# CAN.net
KiCad netlist of a schematic drawn in Altium Designer
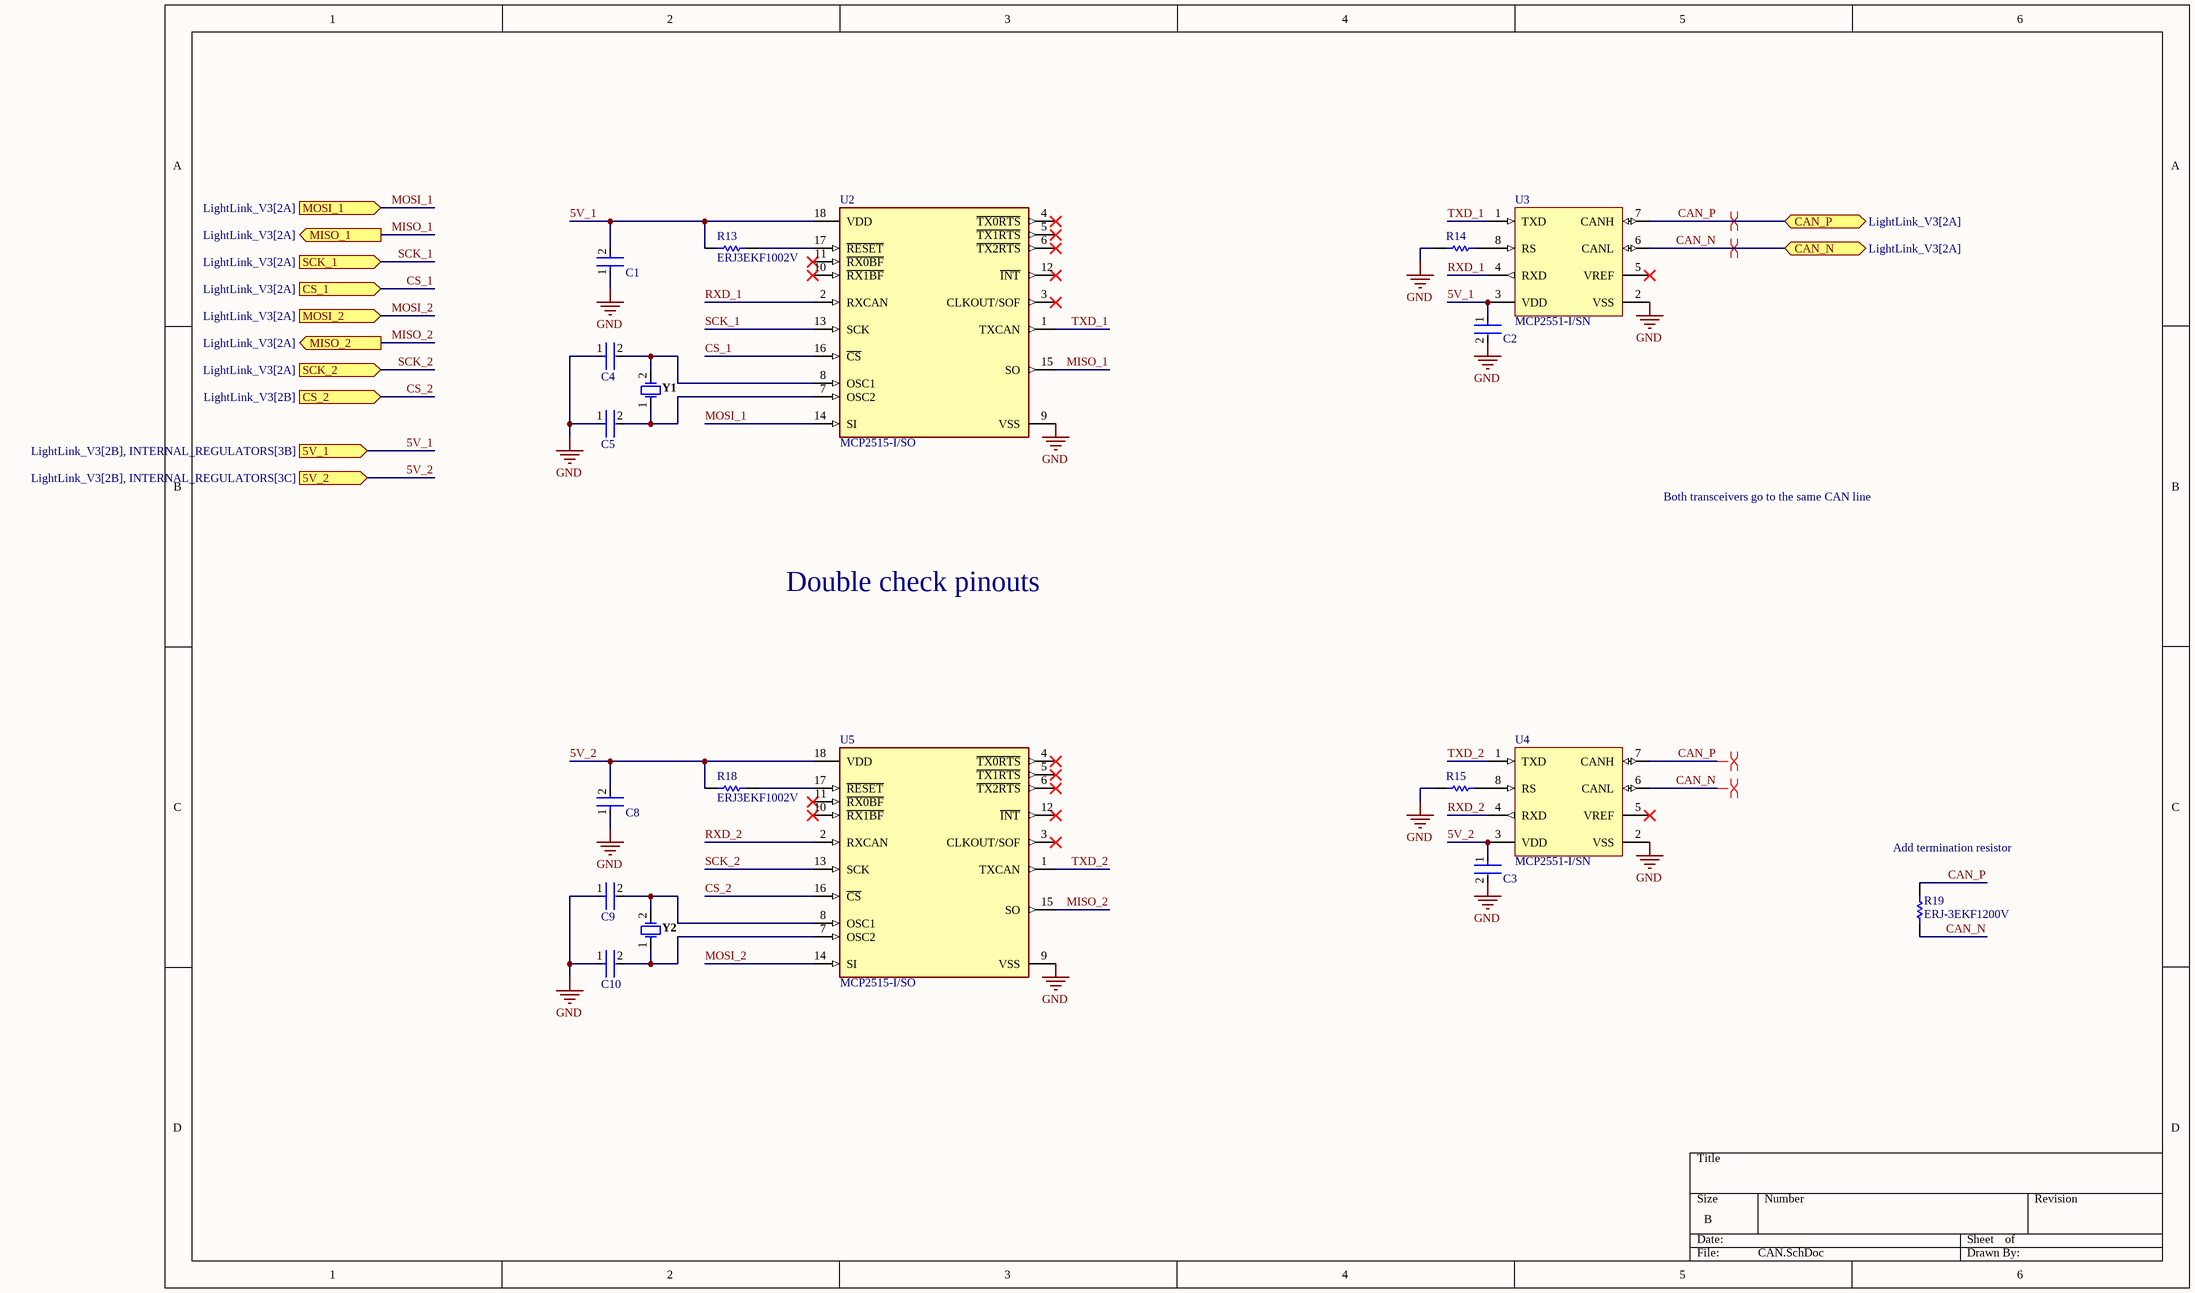
[diagram p0: CAN.SchDoc]

(export (version "E")
  (design (tool "Eeschema 10.0.6"))
  (components
    (comp (ref "C1")
      (value "GRM188R60J106ME47D")
      (footprint "FP-GRM188-0_1-e0_2_0_55-IPC_A")
      (description "Chip Multilayer Ceramic Capacitors for General Purpose, 0603, 10uF, X5R, 15%, 20%, 6.3V")
      (fields (field (name "VOLTAGE") "6.3V") (field (name "TOLERANCE") "20%"))
      (libsource (lib "Altium Content Vault") (part "02cd4be3c70576c341d710602a673aa"))
    )
    (comp (ref "C2")
      (value "C0402C104K8PACTU")
      (footprint "FP-C0402-BB-MFG")
      (description "CAP CER 0.1UF 10V X5R 0402")
      (fields (field (name "MANUFACTURER") "Kemet") (field (name "TOLERANCE") "0.1"))
      (libsource (lib "Altium Content Vault") (part "b4654b650e69147ec39a6b967a45e02"))
    )
    (comp (ref "C3")
      (value "C0402C104K8PACTU")
      (footprint "FP-C0402-BB-MFG")
      (description "CAP CER 0.1UF 10V X5R 0402")
      (fields (field (name "MANUFACTURER") "Kemet") (field (name "TOLERANCE") "0.1"))
      (libsource (lib "Altium Content Vault") (part "b4654b650e69147ec39a6b967a45e02"))
    )
    (comp (ref "C4")
      (value "GRM188R60J106ME47D")
      (footprint "FP-GRM188-0_1-e0_2_0_55-IPC_A")
      (description "Chip Multilayer Ceramic Capacitors for General Purpose, 0603, 10uF, X5R, 15%, 20%, 6.3V")
      (fields (field (name "VOLTAGE") "6.3V") (field (name "TOLERANCE") "20%"))
      (libsource (lib "Altium Content Vault") (part "02cd4be3c70576c341d710602a673aa"))
    )
    (comp (ref "C5")
      (value "GRM188R60J106ME47D")
      (footprint "FP-GRM188-0_1-e0_2_0_55-IPC_A")
      (description "Chip Multilayer Ceramic Capacitors for General Purpose, 0603, 10uF, X5R, 15%, 20%, 6.3V")
      (fields (field (name "VOLTAGE") "6.3V") (field (name "TOLERANCE") "20%"))
      (libsource (lib "Altium Content Vault") (part "02cd4be3c70576c341d710602a673aa"))
    )
    (comp (ref "C8")
      (value "GRM188R60J106ME47D")
      (footprint "FP-GRM188-0_1-e0_2_0_55-IPC_A")
      (description "Chip Multilayer Ceramic Capacitors for General Purpose, 0603, 10uF, X5R, 15%, 20%, 6.3V")
      (fields (field (name "VOLTAGE") "6.3V") (field (name "TOLERANCE") "20%"))
      (libsource (lib "Altium Content Vault") (part "02cd4be3c70576c341d710602a673aa"))
    )
    (comp (ref "C9")
      (value "GRM188R60J106ME47D")
      (footprint "FP-GRM188-0_1-e0_2_0_55-IPC_A")
      (description "Chip Multilayer Ceramic Capacitors for General Purpose, 0603, 10uF, X5R, 15%, 20%, 6.3V")
      (fields (field (name "VOLTAGE") "6.3V") (field (name "TOLERANCE") "20%"))
      (libsource (lib "Altium Content Vault") (part "02cd4be3c70576c341d710602a673aa"))
    )
    (comp (ref "C10")
      (value "GRM188R60J106ME47D")
      (footprint "FP-GRM188-0_1-e0_2_0_55-IPC_A")
      (description "Chip Multilayer Ceramic Capacitors for General Purpose, 0603, 10uF, X5R, 15%, 20%, 6.3V")
      (fields (field (name "VOLTAGE") "6.3V") (field (name "TOLERANCE") "20%"))
      (libsource (lib "Altium Content Vault") (part "02cd4be3c70576c341d710602a673aa"))
    )
    (comp (ref "R13")
      (value "ERJ3EKF1002V")
      (footprint "RESC1609X55X30LL15T15")
      (description "Chip Resistor, 10 KOhm, +/- 1%, 0.1 W, -55 to 155 degC, 0603 (1608 Metric), RoHS, Tape and Reel")
      (fields (field (name "TOLERANCE") "1%") (field (name "MANUFACTURER") "Panasonic"))
      (libsource (lib "Altium Content Vault") (part "RES-2"))
    )
    (comp (ref "R14")
      (value "ERJ3EKF1002V")
      (footprint "RESC1609X55X30LL15T15")
      (description "Chip Resistor, 10 KOhm, +/- 1%, 0.1 W, -55 to 155 degC, 0603 (1608 Metric), RoHS, Tape and Reel")
      (fields (field (name "TOLERANCE") "1%") (field (name "MANUFACTURER") "Panasonic"))
      (libsource (lib "Altium Content Vault") (part "RES-2"))
    )
    (comp (ref "R15")
      (value "ERJ3EKF1002V")
      (footprint "RESC1609X55X30LL15T15")
      (description "Chip Resistor, 10 KOhm, +/- 1%, 0.1 W, -55 to 155 degC, 0603 (1608 Metric), RoHS, Tape and Reel")
      (fields (field (name "TOLERANCE") "1%") (field (name "MANUFACTURER") "Panasonic"))
      (libsource (lib "Altium Content Vault") (part "RES-2"))
    )
    (comp (ref "R18")
      (value "ERJ3EKF1002V")
      (footprint "RESC1609X55X30LL15T15")
      (description "Chip Resistor, 10 KOhm, +/- 1%, 0.1 W, -55 to 155 degC, 0603 (1608 Metric), RoHS, Tape and Reel")
      (fields (field (name "TOLERANCE") "1%") (field (name "MANUFACTURER") "Panasonic"))
      (libsource (lib "Altium Content Vault") (part "RES-2"))
    )
    (comp (ref "R19")
      (value "ERJ-3EKF1200V")
      (footprint "RESC1609X55X30ML15T15")
      (description "Chip Resistor, 120 Ohm, +/- 1%, 0.1 W, -55 to 155 degC, 0603 (1608 Metric), RoHS, Tape and Reel")
      (fields (field (name "TOLERANCE") "1%") (field (name "MANUFACTURER") "Panasonic"))
      (libsource (lib "Altium Content Vault") (part "RES-2"))
    )
    (comp (ref "U2")
      (value "MCP2515-I/SO")
      (footprint "FP-C04-051-MFG")
      (description "IC CAN CONTROLLER W/SPI 18SOIC")
      (fields
        (field (name "MANUFACTURER") "Microchip")
        (field (name "OCTOPART") "https://octopart.com/mcp2515-i%2Fso-microchip-430187")
      )
      (libsource (lib "Altium Content Vault") (part "1c78ea6ff576bac94664e2637e1b479"))
    )
    (comp (ref "U3")
      (value "MCP2551-I/SN")
      (footprint "MCHP-SN8_V")
      (fields (field (name "MANUFACTURER") "Microchip"))
      (libsource (lib "Altium Content Vault") (part "MCHP-MCP2551-SN8"))
    )
    (comp (ref "U4")
      (value "MCP2551-I/SN")
      (footprint "MCHP-SN8_V")
      (fields (field (name "MANUFACTURER") "Microchip"))
      (libsource (lib "Altium Content Vault") (part "MCHP-MCP2551-SN8"))
    )
    (comp (ref "U5")
      (value "MCP2515-I/SO")
      (footprint "FP-C04-051-MFG")
      (description "IC CAN CONTROLLER W/SPI 18SOIC")
      (fields
        (field (name "MANUFACTURER") "Microchip")
        (field (name "OCTOPART") "https://octopart.com/mcp2515-i%2Fso-microchip-430187")
      )
      (libsource (lib "Altium Content Vault") (part "1c78ea6ff576bac94664e2637e1b479"))
    )
    (comp (ref "Y1")
      (value "FOXSLF/160-20")
      (footprint "FOX-FOXSLF160-20")
      (description "Resistance Weld Thru-Hole Crystal, 16 MHz, -20 to 70 degC, 2-Pin THD, RoHS, Bulk")
      (fields (field (name "TOLERANCE") "1%"))
      (libsource (lib "Altium Content Vault") (part "XTAL-1-2-2"))
    )
    (comp (ref "Y2")
      (value "FOXSLF/160-20")
      (footprint "FOX-FOXSLF160-20")
      (description "Resistance Weld Thru-Hole Crystal, 16 MHz, -20 to 70 degC, 2-Pin THD, RoHS, Bulk")
      (fields (field (name "TOLERANCE") "1%"))
      (libsource (lib "Altium Content Vault") (part "XTAL-1-2-2"))
    )
  )
  (nets
    (net (code "1") (name "/5V_1") (class "Default")
      (node (ref "C1") (pin "2") (pinfunction "2_2") (pintype "passive"))
      (node (ref "C2") (pin "1") (pinfunction "1_1") (pintype "passive"))
      (node (ref "R13") (pin "1") (pinfunction "1_1") (pintype "passive"))
      (node (ref "U2") (pin "18") (pinfunction "VDD_18") (pintype "power_in"))
      (node (ref "U3") (pin "3") (pinfunction "VDD_3") (pintype "power_in"))
    )
    (net (code "2") (name "/5V_2") (class "Default")
      (node (ref "C3") (pin "1") (pinfunction "1_1") (pintype "passive"))
      (node (ref "C8") (pin "2") (pinfunction "2_2") (pintype "passive"))
      (node (ref "R18") (pin "1") (pinfunction "1_1") (pintype "passive"))
      (node (ref "U4") (pin "3") (pinfunction "VDD_3") (pintype "power_in"))
      (node (ref "U5") (pin "18") (pinfunction "VDD_18") (pintype "power_in"))
    )
    (net (code "3") (name "/CAN_N") (class "Default")
      (node (ref "R19") (pin "1") (pinfunction "1_1") (pintype "passive"))
      (node (ref "U3") (pin "6") (pinfunction "CANL_6") (pintype "bidirectional"))
      (node (ref "U4") (pin "6") (pinfunction "CANL_6") (pintype "bidirectional"))
    )
    (net (code "4") (name "/CAN_P") (class "Default")
      (node (ref "R19") (pin "2") (pinfunction "2_2") (pintype "passive"))
      (node (ref "U3") (pin "7") (pinfunction "CANH_7") (pintype "bidirectional"))
      (node (ref "U4") (pin "7") (pinfunction "CANH_7") (pintype "bidirectional"))
    )
    (net (code "5") (name "/CS_1") (class "Default")
      (node (ref "U2") (pin "16") (pinfunction "~{CS}_16") (pintype "input"))
    )
    (net (code "6") (name "/CS_2") (class "Default")
      (node (ref "U5") (pin "16") (pinfunction "~{CS}_16") (pintype "input"))
    )
    (net (code "7") (name "/MISO_1") (class "Default")
      (node (ref "U2") (pin "15") (pinfunction "SO_15") (pintype "output"))
    )
    (net (code "8") (name "/MISO_2") (class "Default")
      (node (ref "U5") (pin "15") (pinfunction "SO_15") (pintype "output"))
    )
    (net (code "9") (name "/MOSI_1") (class "Default")
      (node (ref "U2") (pin "14") (pinfunction "SI_14") (pintype "input"))
    )
    (net (code "10") (name "/MOSI_2") (class "Default")
      (node (ref "U5") (pin "14") (pinfunction "SI_14") (pintype "input"))
    )
    (net (code "11") (name "/RXD_1") (class "Default")
      (node (ref "U2") (pin "2") (pinfunction "RXCAN_2") (pintype "input"))
      (node (ref "U3") (pin "4") (pinfunction "RXD_4") (pintype "output"))
    )
    (net (code "12") (name "/RXD_2") (class "Default")
      (node (ref "U4") (pin "4") (pinfunction "RXD_4") (pintype "output"))
      (node (ref "U5") (pin "2") (pinfunction "RXCAN_2") (pintype "input"))
    )
    (net (code "13") (name "/SCK_1") (class "Default")
      (node (ref "U2") (pin "13") (pinfunction "SCK_13") (pintype "input"))
    )
    (net (code "14") (name "/SCK_2") (class "Default")
      (node (ref "U5") (pin "13") (pinfunction "SCK_13") (pintype "input"))
    )
    (net (code "15") (name "/TXD_1") (class "Default")
      (node (ref "U2") (pin "1") (pinfunction "TXCAN_1") (pintype "output"))
      (node (ref "U3") (pin "1") (pinfunction "TXD_1") (pintype "input"))
    )
    (net (code "16") (name "/TXD_2") (class "Default")
      (node (ref "U4") (pin "1") (pinfunction "TXD_1") (pintype "input"))
      (node (ref "U5") (pin "1") (pinfunction "TXCAN_1") (pintype "output"))
    )
    (net (code "17") (name "GND") (class "Default")
      (node (ref "C1") (pin "1") (pinfunction "1_1") (pintype "passive"))
      (node (ref "C10") (pin "1") (pinfunction "1_1") (pintype "passive"))
      (node (ref "C2") (pin "2") (pinfunction "2_2") (pintype "passive"))
      (node (ref "C3") (pin "2") (pinfunction "2_2") (pintype "passive"))
      (node (ref "C4") (pin "1") (pinfunction "1_1") (pintype "passive"))
      (node (ref "C5") (pin "1") (pinfunction "1_1") (pintype "passive"))
      (node (ref "C8") (pin "1") (pinfunction "1_1") (pintype "passive"))
      (node (ref "C9") (pin "1") (pinfunction "1_1") (pintype "passive"))
      (node (ref "R14") (pin "1") (pinfunction "1_1") (pintype "passive"))
      (node (ref "R15") (pin "1") (pinfunction "1_1") (pintype "passive"))
      (node (ref "U2") (pin "9") (pinfunction "VSS_9") (pintype "power_in"))
      (node (ref "U3") (pin "2") (pinfunction "VSS_2") (pintype "power_in"))
      (node (ref "U4") (pin "2") (pinfunction "VSS_2") (pintype "power_in"))
      (node (ref "U5") (pin "9") (pinfunction "VSS_9") (pintype "power_in"))
    )
    (net (code "18") (name "Net-(U2-OSC1)") (class "Default")
      (node (ref "C4") (pin "2") (pinfunction "2_2") (pintype "passive"))
      (node (ref "U2") (pin "8") (pinfunction "OSC1_8") (pintype "input"))
      (node (ref "Y1") (pin "2") (pinfunction "2_2") (pintype "passive"))
    )
    (net (code "19") (name "Net-(U2-OSC2)") (class "Default")
      (node (ref "C5") (pin "2") (pinfunction "2_2") (pintype "passive"))
      (node (ref "U2") (pin "7") (pinfunction "OSC2_7") (pintype "input"))
      (node (ref "Y1") (pin "1") (pinfunction "1_1") (pintype "passive"))
    )
    (net (code "20") (name "Net-(U2-~{RESET})") (class "Default")
      (node (ref "R13") (pin "2") (pinfunction "2_2") (pintype "passive"))
      (node (ref "U2") (pin "17") (pinfunction "~{RESET}_17") (pintype "input"))
    )
    (net (code "21") (name "Net-(U3-RS)") (class "Default")
      (node (ref "R14") (pin "2") (pinfunction "2_2") (pintype "passive"))
      (node (ref "U3") (pin "8") (pinfunction "RS_8") (pintype "input"))
    )
    (net (code "22") (name "Net-(U4-RS)") (class "Default")
      (node (ref "R15") (pin "2") (pinfunction "2_2") (pintype "passive"))
      (node (ref "U4") (pin "8") (pinfunction "RS_8") (pintype "input"))
    )
    (net (code "23") (name "Net-(U5-OSC1)") (class "Default")
      (node (ref "C9") (pin "2") (pinfunction "2_2") (pintype "passive"))
      (node (ref "U5") (pin "8") (pinfunction "OSC1_8") (pintype "input"))
      (node (ref "Y2") (pin "2") (pinfunction "2_2") (pintype "passive"))
    )
    (net (code "24") (name "Net-(U5-OSC2)") (class "Default")
      (node (ref "C10") (pin "2") (pinfunction "2_2") (pintype "passive"))
      (node (ref "U5") (pin "7") (pinfunction "OSC2_7") (pintype "input"))
      (node (ref "Y2") (pin "1") (pinfunction "1_1") (pintype "passive"))
    )
    (net (code "25") (name "Net-(U5-~{RESET})") (class "Default")
      (node (ref "R18") (pin "2") (pinfunction "2_2") (pintype "passive"))
      (node (ref "U5") (pin "17") (pinfunction "~{RESET}_17") (pintype "input"))
    )
    (net (code "26") (name "unconnected-(U2-CLKOUT{slash}SOF-Pad3)") (class "Default")
      (node (ref "U2") (pin "3") (pinfunction "CLKOUT/SOF_3") (pintype "output+no_connect"))
    )
    (net (code "27") (name "unconnected-(U2-~{INT}-Pad12)") (class "Default")
      (node (ref "U2") (pin "12") (pinfunction "~{INT}_12") (pintype "output+no_connect"))
    )
    (net (code "28") (name "unconnected-(U2-~{RX0BF}-Pad11)") (class "Default")
      (node (ref "U2") (pin "11") (pinfunction "~{RX0BF}_11") (pintype "input+no_connect"))
    )
    (net (code "29") (name "unconnected-(U2-~{RX1BF}-Pad10)") (class "Default")
      (node (ref "U2") (pin "10") (pinfunction "~{RX1BF}_10") (pintype "input+no_connect"))
    )
    (net (code "30") (name "unconnected-(U2-~{TX0RTS}-Pad4)") (class "Default")
      (node (ref "U2") (pin "4") (pinfunction "~{TX0RTS}_4") (pintype "output+no_connect"))
    )
    (net (code "31") (name "unconnected-(U2-~{TX1RTS}-Pad5)") (class "Default")
      (node (ref "U2") (pin "5") (pinfunction "~{TX1RTS}_5") (pintype "output+no_connect"))
    )
    (net (code "32") (name "unconnected-(U2-~{TX2RTS}-Pad6)") (class "Default")
      (node (ref "U2") (pin "6") (pinfunction "~{TX2RTS}_6") (pintype "output+no_connect"))
    )
    (net (code "33") (name "unconnected-(U3-VREF-Pad5)") (class "Default")
      (node (ref "U3") (pin "5") (pinfunction "VREF_5") (pintype "power_in+no_connect"))
    )
    (net (code "34") (name "unconnected-(U4-VREF-Pad5)") (class "Default")
      (node (ref "U4") (pin "5") (pinfunction "VREF_5") (pintype "power_in+no_connect"))
    )
    (net (code "35") (name "unconnected-(U5-CLKOUT{slash}SOF-Pad3)") (class "Default")
      (node (ref "U5") (pin "3") (pinfunction "CLKOUT/SOF_3") (pintype "output+no_connect"))
    )
    (net (code "36") (name "unconnected-(U5-~{INT}-Pad12)") (class "Default")
      (node (ref "U5") (pin "12") (pinfunction "~{INT}_12") (pintype "output+no_connect"))
    )
    (net (code "37") (name "unconnected-(U5-~{RX0BF}-Pad11)") (class "Default")
      (node (ref "U5") (pin "11") (pinfunction "~{RX0BF}_11") (pintype "input+no_connect"))
    )
    (net (code "38") (name "unconnected-(U5-~{RX1BF}-Pad10)") (class "Default")
      (node (ref "U5") (pin "10") (pinfunction "~{RX1BF}_10") (pintype "input+no_connect"))
    )
    (net (code "39") (name "unconnected-(U5-~{TX0RTS}-Pad4)") (class "Default")
      (node (ref "U5") (pin "4") (pinfunction "~{TX0RTS}_4") (pintype "output+no_connect"))
    )
    (net (code "40") (name "unconnected-(U5-~{TX1RTS}-Pad5)") (class "Default")
      (node (ref "U5") (pin "5") (pinfunction "~{TX1RTS}_5") (pintype "output+no_connect"))
    )
    (net (code "41") (name "unconnected-(U5-~{TX2RTS}-Pad6)") (class "Default")
      (node (ref "U5") (pin "6") (pinfunction "~{TX2RTS}_6") (pintype "output+no_connect"))
    )
  )
)
